# motor_controller_link.net
KiCad netlist of a schematic drawn in EAGLE
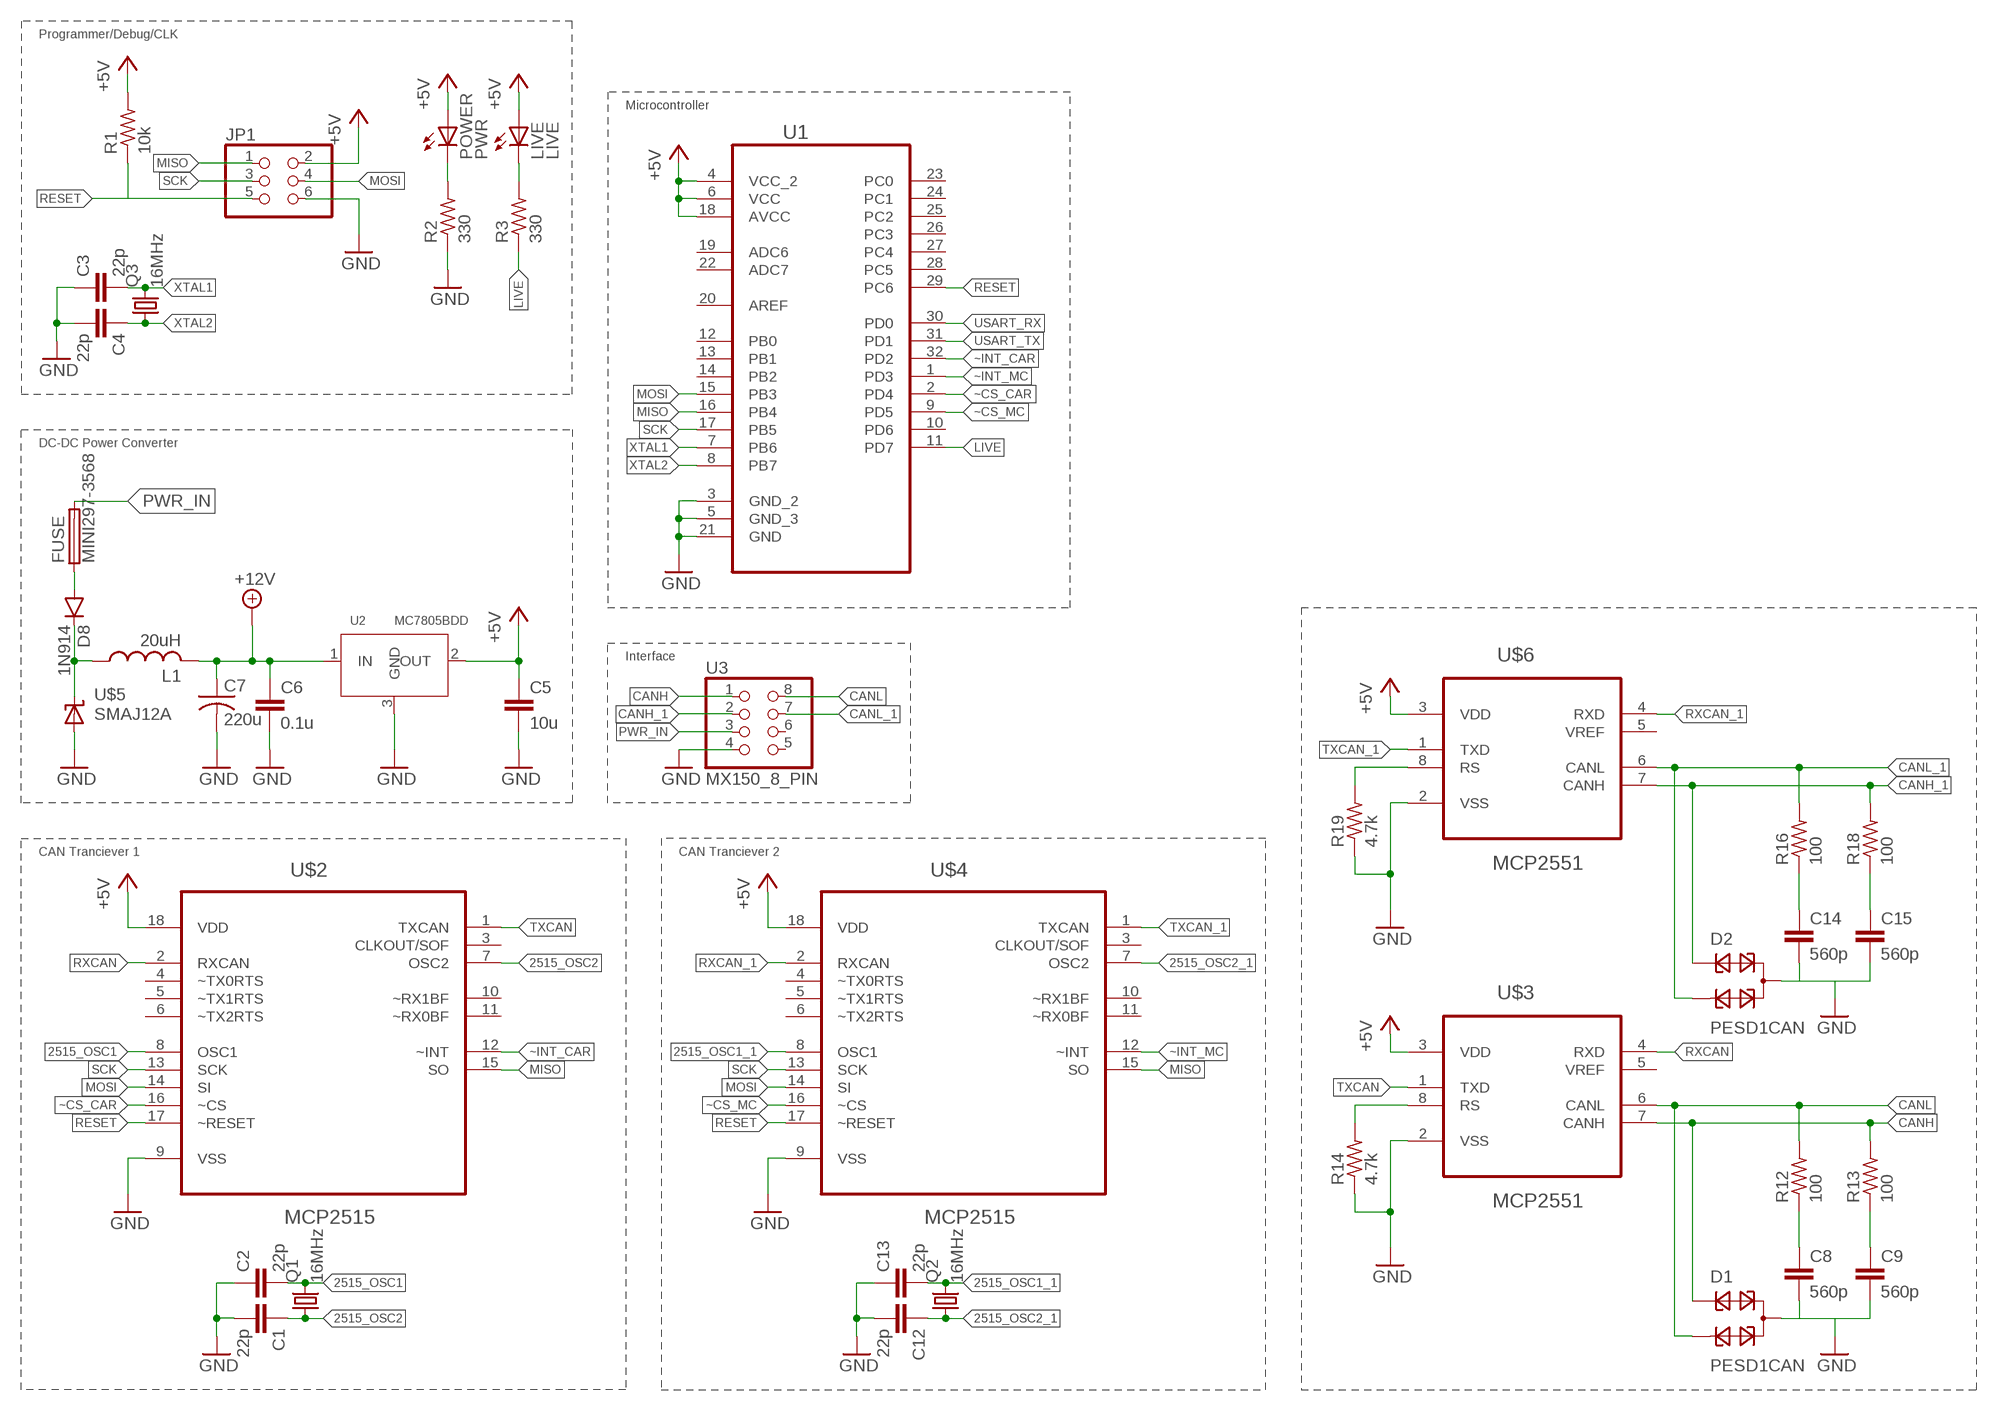
[diagram p0: schematic, sheet 1]

(export (version "E")
  (design (tool "Eeschema 10.0.6"))
  (components
    (comp (ref "C1")
      (value "22p")
      (footprint "eagle-import:C0805K")
      (libsource (lib "eagle-import") (part "resistor_C-EUC0805K"))
    )
    (comp (ref "C2")
      (value "22p")
      (footprint "eagle-import:C0805K")
      (libsource (lib "eagle-import") (part "resistor_C-EUC0805K"))
    )
    (comp (ref "C3")
      (value "22p")
      (footprint "eagle-import:C0805K")
      (libsource (lib "eagle-import") (part "resistor_C-EUC0805K"))
    )
    (comp (ref "C4")
      (value "22p")
      (footprint "eagle-import:C0805K")
      (libsource (lib "eagle-import") (part "resistor_C-EUC0805K"))
    )
    (comp (ref "C5")
      (value "10u")
      (footprint "eagle-import:C0805K")
      (libsource (lib "eagle-import") (part "C-EUC0805K"))
    )
    (comp (ref "C6")
      (value "0.1u")
      (footprint "eagle-import:C0805K")
      (libsource (lib "eagle-import") (part "C-EUC0805K"))
    )
    (comp (ref "C7")
      (value "220u")
      (footprint "eagle-import:C1206")
      (libsource (lib "eagle-import") (part "C1206"))
    )
    (comp (ref "C8")
      (value "560p")
      (footprint "eagle-import:C0805K")
      (libsource (lib "eagle-import") (part "C-EUC0805K"))
    )
    (comp (ref "C9")
      (value "560p")
      (footprint "eagle-import:C0805K")
      (libsource (lib "eagle-import") (part "C-EUC0805K"))
    )
    (comp (ref "C12")
      (value "22p")
      (footprint "eagle-import:C0805K")
      (libsource (lib "eagle-import") (part "resistor_C-EUC0805K"))
    )
    (comp (ref "C13")
      (value "22p")
      (footprint "eagle-import:C0805K")
      (libsource (lib "eagle-import") (part "resistor_C-EUC0805K"))
    )
    (comp (ref "C14")
      (value "560p")
      (footprint "eagle-import:C0805K")
      (libsource (lib "eagle-import") (part "C-EUC0805K"))
    )
    (comp (ref "C15")
      (value "560p")
      (footprint "eagle-import:C0805K")
      (libsource (lib "eagle-import") (part "C-EUC0805K"))
    )
    (comp (ref "D1")
      (value "PESD1CAN")
      (footprint "eagle-import:SOT23")
      (libsource (lib "eagle-import") (part "PESD1CAN"))
    )
    (comp (ref "D2")
      (value "PESD1CAN")
      (footprint "eagle-import:SOT23")
      (libsource (lib "eagle-import") (part "PESD1CAN"))
    )
    (comp (ref "D8")
      (value "1N914")
      (footprint "eagle-import:SMA-DIODE")
      (libsource (lib "eagle-import") (part "DIODESMA"))
    )
    (comp (ref "FUSE")
      (value "MINI297-3568")
      (footprint "eagle-import:3568")
      (libsource (lib "eagle-import") (part "MINI297-3568"))
    )
    (comp (ref "JP1")
      (value "PINHD-2X3")
      (footprint "eagle-import:2X03")
      (libsource (lib "eagle-import") (part "PINHD-2X3"))
    )
    (comp (ref "L1")
      (value "20uH")
      (footprint "eagle-import:MSS7348")
      (libsource (lib "eagle-import") (part "MSS7348"))
    )
    (comp (ref "LIVE")
      (value "LIVE")
      (footprint "eagle-import:SML0805")
      (libsource (lib "eagle-import") (part "LEDSML0805"))
    )
    (comp (ref "POWER")
      (value "PWR")
      (footprint "eagle-import:SML0805")
      (libsource (lib "eagle-import") (part "LEDSML0805"))
    )
    (comp (ref "Q1")
      (value "16MHz")
      (footprint "eagle-import:CTS406")
      (libsource (lib "eagle-import") (part "CRYSTALCTS406"))
    )
    (comp (ref "Q2")
      (value "16MHz")
      (footprint "eagle-import:CTS406")
      (libsource (lib "eagle-import") (part "CRYSTALCTS406"))
    )
    (comp (ref "Q3")
      (value "16MHz")
      (footprint "eagle-import:CTS406")
      (libsource (lib "eagle-import") (part "CRYSTALCTS406"))
    )
    (comp (ref "R1")
      (value "10k")
      (footprint "eagle-import:R0805")
      (libsource (lib "eagle-import") (part "R-US_R0805"))
    )
    (comp (ref "R2")
      (value "330")
      (footprint "eagle-import:R0805")
      (libsource (lib "eagle-import") (part "R-US_R0805"))
    )
    (comp (ref "R3")
      (value "330")
      (footprint "eagle-import:R0805")
      (libsource (lib "eagle-import") (part "R-US_R0805"))
    )
    (comp (ref "R12")
      (value "100")
      (footprint "eagle-import:R0805")
      (libsource (lib "eagle-import") (part "R-US_R0805"))
    )
    (comp (ref "R13")
      (value "100")
      (footprint "eagle-import:R0805")
      (libsource (lib "eagle-import") (part "R-US_R0805"))
    )
    (comp (ref "R14")
      (value "4.7k")
      (footprint "eagle-import:R0805")
      (libsource (lib "eagle-import") (part "R-US_R0805"))
    )
    (comp (ref "R16")
      (value "100")
      (footprint "eagle-import:R0805")
      (libsource (lib "eagle-import") (part "R-US_R0805"))
    )
    (comp (ref "R18")
      (value "100")
      (footprint "eagle-import:R0805")
      (libsource (lib "eagle-import") (part "R-US_R0805"))
    )
    (comp (ref "R19")
      (value "4.7k")
      (footprint "eagle-import:R0805")
      (libsource (lib "eagle-import") (part "R-US_R0805"))
    )
    (comp (ref "U$2")
      (value "MCP2515")
      (footprint "eagle-import:SOIC127P1034X264-18N")
      (fields (field (name "MPN") "MCP2515-I/SO"))
      (libsource (lib "eagle-import") (part "MCP2515-I/SO"))
    )
    (comp (ref "U$3")
      (value "MCP2551")
      (footprint "eagle-import:SOIC127P600X175-8N")
      (fields (field (name "MPN") "MCP2551-I/SN"))
      (libsource (lib "eagle-import") (part "MCP2551-I/SN"))
    )
    (comp (ref "U$4")
      (value "MCP2515")
      (footprint "eagle-import:SOIC127P1034X264-18N")
      (fields (field (name "MPN") "MCP2515-I/SO"))
      (libsource (lib "eagle-import") (part "MCP2515-I/SO"))
    )
    (comp (ref "U$5")
      (value "SMAJ12A")
      (footprint "eagle-import:DO-214AC")
      (libsource (lib "eagle-import") (part "SMAJ12A"))
    )
    (comp (ref "U$6")
      (value "MCP2551")
      (footprint "eagle-import:SOIC127P600X175-8N")
      (fields (field (name "MPN") "MCP2551-I/SN"))
      (libsource (lib "eagle-import") (part "MCP2551-I/SN"))
    )
    (comp (ref "U1")
      (value "ATMEGA328P-AU")
      (footprint "eagle-import:QFP80P900X900X120-32N")
      (libsource (lib "eagle-import") (part "ATMEGA328P-AU"))
    )
    (comp (ref "U2")
      (value "MC7805BDD")
      (footprint "eagle-import:DPAK")
      (libsource (lib "eagle-import") (part "MC7805BDD"))
    )
    (comp (ref "U3")
      (value "MX150_8_PIN")
      (footprint "eagle-import:MX150_8")
      (libsource (lib "eagle-import") (part "MX150_8_PIN"))
    )
  )
  (nets
    (net (code "1") (name "+5V") (class "Default")
      (node (ref "C5") (pin "1") (pinfunction "1_1") (pintype "passive"))
      (node (ref "JP1") (pin "2") (pinfunction "2_2") (pintype "passive"))
      (node (ref "LIVE") (pin "A") (pinfunction "A_A") (pintype "passive"))
      (node (ref "POWER") (pin "A") (pinfunction "A_A") (pintype "passive"))
      (node (ref "R1") (pin "2") (pinfunction "2_2") (pintype "passive"))
      (node (ref "U$2") (pin "18") (pinfunction "VDD_18") (pintype "power_in"))
      (node (ref "U$3") (pin "3") (pinfunction "VDD_3") (pintype "power_in"))
      (node (ref "U$4") (pin "18") (pinfunction "VDD_18") (pintype "power_in"))
      (node (ref "U$6") (pin "3") (pinfunction "VDD_3") (pintype "power_in"))
      (node (ref "U1") (pin "18") (pinfunction "AVCC_18") (pintype "power_in"))
      (node (ref "U1") (pin "4") (pinfunction "VCC_2_4") (pintype "power_in"))
      (node (ref "U1") (pin "6") (pinfunction "VCC_6") (pintype "power_in"))
      (node (ref "U2") (pin "2") (pinfunction "OUT_2") (pintype "bidirectional"))
    )
    (net (code "2") (name "+12V") (class "Default")
      (node (ref "C6") (pin "1") (pinfunction "1_1") (pintype "passive"))
      (node (ref "C7") (pin "1") (pinfunction "1_1") (pintype "passive"))
      (node (ref "L1") (pin "P$2") (pinfunction "2_P$2") (pintype "passive"))
      (node (ref "U2") (pin "1") (pinfunction "IN_1") (pintype "bidirectional"))
    )
    (net (code "3") (name "/~{CS_CAR}") (class "Default")
      (node (ref "U$2") (pin "16") (pinfunction "~{CS}_16") (pintype "input"))
      (node (ref "U1") (pin "2") (pinfunction "PD4_2") (pintype "bidirectional"))
    )
    (net (code "4") (name "/~{CS_MC}") (class "Default")
      (node (ref "U$4") (pin "16") (pinfunction "~{CS}_16") (pintype "input"))
      (node (ref "U1") (pin "9") (pinfunction "PD5_9") (pintype "bidirectional"))
    )
    (net (code "5") (name "/~{INT_CAR}") (class "Default")
      (node (ref "U$2") (pin "12") (pinfunction "~{INT}_12") (pintype "output"))
      (node (ref "U1") (pin "32") (pinfunction "PD2_32") (pintype "bidirectional"))
    )
    (net (code "6") (name "/~{INT_MC}") (class "Default")
      (node (ref "U$4") (pin "12") (pinfunction "~{INT}_12") (pintype "output"))
      (node (ref "U1") (pin "1") (pinfunction "PD3_1") (pintype "bidirectional"))
    )
    (net (code "7") (name "2515_OSC1") (class "Default")
      (node (ref "C2") (pin "2") (pinfunction "2_2") (pintype "passive"))
      (node (ref "Q1") (pin "3") (pinfunction "2_3") (pintype "passive"))
      (node (ref "U$2") (pin "8") (pinfunction "OSC1_8") (pintype "input"))
    )
    (net (code "8") (name "2515_OSC1_1") (class "Default")
      (node (ref "C13") (pin "2") (pinfunction "2_2") (pintype "passive"))
      (node (ref "Q2") (pin "3") (pinfunction "2_3") (pintype "passive"))
      (node (ref "U$4") (pin "8") (pinfunction "OSC1_8") (pintype "input"))
    )
    (net (code "9") (name "2515_OSC2") (class "Default")
      (node (ref "C1") (pin "1") (pinfunction "1_1") (pintype "passive"))
      (node (ref "Q1") (pin "1") (pinfunction "1_1") (pintype "passive"))
      (node (ref "U$2") (pin "7") (pinfunction "OSC2_7") (pintype "output"))
    )
    (net (code "10") (name "2515_OSC2_1") (class "Default")
      (node (ref "C12") (pin "1") (pinfunction "1_1") (pintype "passive"))
      (node (ref "Q2") (pin "1") (pinfunction "1_1") (pintype "passive"))
      (node (ref "U$4") (pin "7") (pinfunction "OSC2_7") (pintype "output"))
    )
    (net (code "11") (name "CANH") (class "Default")
      (node (ref "D1") (pin "1") (pinfunction "1_1") (pintype "passive"))
      (node (ref "R13") (pin "2") (pinfunction "2_2") (pintype "passive"))
      (node (ref "U$3") (pin "7") (pinfunction "CANH_7") (pintype "bidirectional"))
      (node (ref "U3") (pin "1") (pinfunction "1_1") (pintype "passive"))
    )
    (net (code "12") (name "CANH_1") (class "Default")
      (node (ref "D2") (pin "1") (pinfunction "1_1") (pintype "passive"))
      (node (ref "R18") (pin "2") (pinfunction "2_2") (pintype "passive"))
      (node (ref "U$6") (pin "7") (pinfunction "CANH_7") (pintype "bidirectional"))
      (node (ref "U3") (pin "2") (pinfunction "3_2") (pintype "passive"))
    )
    (net (code "13") (name "CANL") (class "Default")
      (node (ref "D1") (pin "2") (pinfunction "2_2") (pintype "passive"))
      (node (ref "R12") (pin "2") (pinfunction "2_2") (pintype "passive"))
      (node (ref "U$3") (pin "6") (pinfunction "CANL_6") (pintype "bidirectional"))
      (node (ref "U3") (pin "8") (pinfunction "2_8") (pintype "passive"))
    )
    (net (code "14") (name "CANL_1") (class "Default")
      (node (ref "D2") (pin "2") (pinfunction "2_2") (pintype "passive"))
      (node (ref "R16") (pin "2") (pinfunction "2_2") (pintype "passive"))
      (node (ref "U$6") (pin "6") (pinfunction "CANL_6") (pintype "bidirectional"))
      (node (ref "U3") (pin "7") (pinfunction "4_7") (pintype "passive"))
    )
    (net (code "15") (name "GND") (class "Default")
      (node (ref "C1") (pin "2") (pinfunction "2_2") (pintype "passive"))
      (node (ref "C12") (pin "2") (pinfunction "2_2") (pintype "passive"))
      (node (ref "C13") (pin "1") (pinfunction "1_1") (pintype "passive"))
      (node (ref "C14") (pin "2") (pinfunction "2_2") (pintype "passive"))
      (node (ref "C15") (pin "2") (pinfunction "2_2") (pintype "passive"))
      (node (ref "C2") (pin "1") (pinfunction "1_1") (pintype "passive"))
      (node (ref "C3") (pin "1") (pinfunction "1_1") (pintype "passive"))
      (node (ref "C4") (pin "2") (pinfunction "2_2") (pintype "passive"))
      (node (ref "C5") (pin "2") (pinfunction "2_2") (pintype "passive"))
      (node (ref "C6") (pin "2") (pinfunction "2_2") (pintype "passive"))
      (node (ref "C7") (pin "2") (pinfunction "2_2") (pintype "passive"))
      (node (ref "C8") (pin "2") (pinfunction "2_2") (pintype "passive"))
      (node (ref "C9") (pin "2") (pinfunction "2_2") (pintype "passive"))
      (node (ref "D1") (pin "3") (pinfunction "3_3") (pintype "passive"))
      (node (ref "D2") (pin "3") (pinfunction "3_3") (pintype "passive"))
      (node (ref "JP1") (pin "6") (pinfunction "6_6") (pintype "passive"))
      (node (ref "R14") (pin "1") (pinfunction "1_1") (pintype "passive"))
      (node (ref "R19") (pin "1") (pinfunction "1_1") (pintype "passive"))
      (node (ref "R2") (pin "1") (pinfunction "1_1") (pintype "passive"))
      (node (ref "U$2") (pin "9") (pinfunction "VSS_9") (pintype "power_in"))
      (node (ref "U$3") (pin "2") (pinfunction "VSS_2") (pintype "passive"))
      (node (ref "U$4") (pin "9") (pinfunction "VSS_9") (pintype "power_in"))
      (node (ref "U$5") (pin "A") (pinfunction "A_A") (pintype "passive"))
      (node (ref "U$6") (pin "2") (pinfunction "VSS_2") (pintype "passive"))
      (node (ref "U1") (pin "21") (pinfunction "GND_21") (pintype "passive"))
      (node (ref "U1") (pin "3") (pinfunction "GND_2_3") (pintype "passive"))
      (node (ref "U1") (pin "5") (pinfunction "GND_3_5") (pintype "passive"))
      (node (ref "U2") (pin "3") (pinfunction "GND_3") (pintype "bidirectional"))
      (node (ref "U3") (pin "4") (pinfunction "7_4") (pintype "passive"))
    )
    (net (code "16") (name "LIVE") (class "Default")
      (node (ref "R3") (pin "1") (pinfunction "1_1") (pintype "passive"))
      (node (ref "U1") (pin "11") (pinfunction "PD7_11") (pintype "bidirectional"))
    )
    (net (code "17") (name "MISO") (class "Default")
      (node (ref "JP1") (pin "1") (pinfunction "1_1") (pintype "passive"))
      (node (ref "U$2") (pin "15") (pinfunction "SO_15") (pintype "output"))
      (node (ref "U$4") (pin "15") (pinfunction "SO_15") (pintype "output"))
      (node (ref "U1") (pin "16") (pinfunction "PB4_16") (pintype "bidirectional"))
    )
    (net (code "18") (name "MOSI") (class "Default")
      (node (ref "JP1") (pin "4") (pinfunction "4_4") (pintype "passive"))
      (node (ref "U$2") (pin "14") (pinfunction "SI_14") (pintype "input"))
      (node (ref "U$4") (pin "14") (pinfunction "SI_14") (pintype "input"))
      (node (ref "U1") (pin "15") (pinfunction "PB3_15") (pintype "bidirectional"))
    )
    (net (code "19") (name "Net-(C8-Pad1)") (class "Default")
      (node (ref "C8") (pin "1") (pinfunction "1_1") (pintype "passive"))
      (node (ref "R12") (pin "1") (pinfunction "1_1") (pintype "passive"))
    )
    (net (code "20") (name "Net-(C9-Pad1)") (class "Default")
      (node (ref "C9") (pin "1") (pinfunction "1_1") (pintype "passive"))
      (node (ref "R13") (pin "1") (pinfunction "1_1") (pintype "passive"))
    )
    (net (code "21") (name "Net-(C14-Pad1)") (class "Default")
      (node (ref "C14") (pin "1") (pinfunction "1_1") (pintype "passive"))
      (node (ref "R16") (pin "1") (pinfunction "1_1") (pintype "passive"))
    )
    (net (code "22") (name "Net-(C15-Pad1)") (class "Default")
      (node (ref "C15") (pin "1") (pinfunction "1_1") (pintype "passive"))
      (node (ref "R18") (pin "1") (pinfunction "1_1") (pintype "passive"))
    )
    (net (code "23") (name "Net-(D8-PadA)") (class "Default")
      (node (ref "D8") (pin "A") (pinfunction "A_A") (pintype "passive"))
      (node (ref "FUSE") (pin "P$1") (pinfunction "1_P$1") (pintype "passive"))
      (node (ref "FUSE") (pin "P$4") (pinfunction "1_P$4") (pintype "passive"))
    )
    (net (code "24") (name "Net-(L1-1)") (class "Default")
      (node (ref "D8") (pin "C") (pinfunction "C_C") (pintype "passive"))
      (node (ref "L1") (pin "P$1") (pinfunction "1_P$1") (pintype "passive"))
      (node (ref "U$5") (pin "C") (pinfunction "C_C") (pintype "passive"))
    )
    (net (code "25") (name "Net-(LIVE-PadC)") (class "Default")
      (node (ref "LIVE") (pin "C") (pinfunction "C_C") (pintype "passive"))
      (node (ref "R3") (pin "2") (pinfunction "2_2") (pintype "passive"))
    )
    (net (code "26") (name "Net-(POWER-PadC)") (class "Default")
      (node (ref "POWER") (pin "C") (pinfunction "C_C") (pintype "passive"))
      (node (ref "R2") (pin "2") (pinfunction "2_2") (pintype "passive"))
    )
    (net (code "27") (name "Net-(U$3-RS)") (class "Default")
      (node (ref "R14") (pin "2") (pinfunction "2_2") (pintype "passive"))
      (node (ref "U$3") (pin "8") (pinfunction "RS_8") (pintype "input"))
    )
    (net (code "28") (name "Net-(U$6-RS)") (class "Default")
      (node (ref "R19") (pin "2") (pinfunction "2_2") (pintype "passive"))
      (node (ref "U$6") (pin "8") (pinfunction "RS_8") (pintype "input"))
    )
    (net (code "29") (name "PWR_IN") (class "Default")
      (node (ref "FUSE") (pin "P$2") (pinfunction "2_P$2") (pintype "passive"))
      (node (ref "FUSE") (pin "P$3") (pinfunction "2_P$3") (pintype "passive"))
      (node (ref "U3") (pin "3") (pinfunction "5_3") (pintype "passive"))
    )
    (net (code "30") (name "RESET") (class "Default")
      (node (ref "JP1") (pin "5") (pinfunction "5_5") (pintype "passive"))
      (node (ref "R1") (pin "1") (pinfunction "1_1") (pintype "passive"))
      (node (ref "U$2") (pin "17") (pinfunction "~{RESET}_17") (pintype "input"))
      (node (ref "U$4") (pin "17") (pinfunction "~{RESET}_17") (pintype "input"))
      (node (ref "U1") (pin "29") (pinfunction "PC6_29") (pintype "bidirectional"))
    )
    (net (code "31") (name "RXCAN") (class "Default")
      (node (ref "U$2") (pin "2") (pinfunction "RXCAN_2") (pintype "input"))
      (node (ref "U$3") (pin "4") (pinfunction "RXD_4") (pintype "output"))
    )
    (net (code "32") (name "RXCAN_1") (class "Default")
      (node (ref "U$4") (pin "2") (pinfunction "RXCAN_2") (pintype "input"))
      (node (ref "U$6") (pin "4") (pinfunction "RXD_4") (pintype "output"))
    )
    (net (code "33") (name "SCK") (class "Default")
      (node (ref "JP1") (pin "3") (pinfunction "3_3") (pintype "passive"))
      (node (ref "U$2") (pin "13") (pinfunction "SCK_13") (pintype "input"))
      (node (ref "U$4") (pin "13") (pinfunction "SCK_13") (pintype "input"))
      (node (ref "U1") (pin "17") (pinfunction "PB5_17") (pintype "bidirectional"))
    )
    (net (code "34") (name "TXCAN") (class "Default")
      (node (ref "U$2") (pin "1") (pinfunction "TXCAN_1") (pintype "output"))
      (node (ref "U$3") (pin "1") (pinfunction "TXD_1") (pintype "input"))
    )
    (net (code "35") (name "TXCAN_1") (class "Default")
      (node (ref "U$4") (pin "1") (pinfunction "TXCAN_1") (pintype "output"))
      (node (ref "U$6") (pin "1") (pinfunction "TXD_1") (pintype "input"))
    )
    (net (code "36") (name "USART_RX") (class "Default")
      (node (ref "U1") (pin "30") (pinfunction "PD0_30") (pintype "bidirectional"))
    )
    (net (code "37") (name "USART_TX") (class "Default")
      (node (ref "U1") (pin "31") (pinfunction "PD1_31") (pintype "bidirectional"))
    )
    (net (code "38") (name "XTAL1") (class "Default")
      (node (ref "C3") (pin "2") (pinfunction "2_2") (pintype "passive"))
      (node (ref "Q3") (pin "3") (pinfunction "2_3") (pintype "passive"))
      (node (ref "U1") (pin "7") (pinfunction "PB6_7") (pintype "bidirectional"))
    )
    (net (code "39") (name "XTAL2") (class "Default")
      (node (ref "C4") (pin "1") (pinfunction "1_1") (pintype "passive"))
      (node (ref "Q3") (pin "1") (pinfunction "1_1") (pintype "passive"))
      (node (ref "U1") (pin "8") (pinfunction "PB7_8") (pintype "bidirectional"))
    )
    (net (code "40") (name "unconnected-(U$2-CLKOUT{slash}SOF-Pad3)") (class "Default")
      (node (ref "U$2") (pin "3") (pinfunction "CLKOUT/SOF_3") (pintype "output"))
    )
    (net (code "41") (name "unconnected-(U$2-~{RX0BF}-Pad11)") (class "Default")
      (node (ref "U$2") (pin "11") (pinfunction "~{RX0BF}_11") (pintype "output"))
    )
    (net (code "42") (name "unconnected-(U$2-~{RX1BF}-Pad10)") (class "Default")
      (node (ref "U$2") (pin "10") (pinfunction "~{RX1BF}_10") (pintype "output"))
    )
    (net (code "43") (name "unconnected-(U$2-~{TX0RTS}-Pad4)") (class "Default")
      (node (ref "U$2") (pin "4") (pinfunction "~{TX0RTS}_4") (pintype "input"))
    )
    (net (code "44") (name "unconnected-(U$2-~{TX1RTS}-Pad5)") (class "Default")
      (node (ref "U$2") (pin "5") (pinfunction "~{TX1RTS}_5") (pintype "input"))
    )
    (net (code "45") (name "unconnected-(U$2-~{TX2RTS}-Pad6)") (class "Default")
      (node (ref "U$2") (pin "6") (pinfunction "~{TX2RTS}_6") (pintype "input"))
    )
    (net (code "46") (name "unconnected-(U$3-VREF-Pad5)") (class "Default")
      (node (ref "U$3") (pin "5") (pinfunction "VREF_5") (pintype "output"))
    )
    (net (code "47") (name "unconnected-(U$4-CLKOUT{slash}SOF-Pad3)") (class "Default")
      (node (ref "U$4") (pin "3") (pinfunction "CLKOUT/SOF_3") (pintype "output"))
    )
    (net (code "48") (name "unconnected-(U$4-~{RX0BF}-Pad11)") (class "Default")
      (node (ref "U$4") (pin "11") (pinfunction "~{RX0BF}_11") (pintype "output"))
    )
    (net (code "49") (name "unconnected-(U$4-~{RX1BF}-Pad10)") (class "Default")
      (node (ref "U$4") (pin "10") (pinfunction "~{RX1BF}_10") (pintype "output"))
    )
    (net (code "50") (name "unconnected-(U$4-~{TX0RTS}-Pad4)") (class "Default")
      (node (ref "U$4") (pin "4") (pinfunction "~{TX0RTS}_4") (pintype "input"))
    )
    (net (code "51") (name "unconnected-(U$4-~{TX1RTS}-Pad5)") (class "Default")
      (node (ref "U$4") (pin "5") (pinfunction "~{TX1RTS}_5") (pintype "input"))
    )
    (net (code "52") (name "unconnected-(U$4-~{TX2RTS}-Pad6)") (class "Default")
      (node (ref "U$4") (pin "6") (pinfunction "~{TX2RTS}_6") (pintype "input"))
    )
    (net (code "53") (name "unconnected-(U$6-VREF-Pad5)") (class "Default")
      (node (ref "U$6") (pin "5") (pinfunction "VREF_5") (pintype "output"))
    )
    (net (code "54") (name "unconnected-(U1-ADC6-Pad19)") (class "Default")
      (node (ref "U1") (pin "19") (pinfunction "ADC6_19") (pintype "input"))
    )
    (net (code "55") (name "unconnected-(U1-ADC7-Pad22)") (class "Default")
      (node (ref "U1") (pin "22") (pinfunction "ADC7_22") (pintype "input"))
    )
    (net (code "56") (name "unconnected-(U1-AREF-Pad20)") (class "Default")
      (node (ref "U1") (pin "20") (pinfunction "AREF_20") (pintype "input"))
    )
    (net (code "57") (name "unconnected-(U1-PB0-Pad12)") (class "Default")
      (node (ref "U1") (pin "12") (pinfunction "PB0_12") (pintype "bidirectional"))
    )
    (net (code "58") (name "unconnected-(U1-PB1-Pad13)") (class "Default")
      (node (ref "U1") (pin "13") (pinfunction "PB1_13") (pintype "bidirectional"))
    )
    (net (code "59") (name "unconnected-(U1-PB2-Pad14)") (class "Default")
      (node (ref "U1") (pin "14") (pinfunction "PB2_14") (pintype "bidirectional"))
    )
    (net (code "60") (name "unconnected-(U1-PC0-Pad23)") (class "Default")
      (node (ref "U1") (pin "23") (pinfunction "PC0_23") (pintype "bidirectional"))
    )
    (net (code "61") (name "unconnected-(U1-PC1-Pad24)") (class "Default")
      (node (ref "U1") (pin "24") (pinfunction "PC1_24") (pintype "bidirectional"))
    )
    (net (code "62") (name "unconnected-(U1-PC2-Pad25)") (class "Default")
      (node (ref "U1") (pin "25") (pinfunction "PC2_25") (pintype "bidirectional"))
    )
    (net (code "63") (name "unconnected-(U1-PC3-Pad26)") (class "Default")
      (node (ref "U1") (pin "26") (pinfunction "PC3_26") (pintype "bidirectional"))
    )
    (net (code "64") (name "unconnected-(U1-PC4-Pad27)") (class "Default")
      (node (ref "U1") (pin "27") (pinfunction "PC4_27") (pintype "bidirectional"))
    )
    (net (code "65") (name "unconnected-(U1-PC5-Pad28)") (class "Default")
      (node (ref "U1") (pin "28") (pinfunction "PC5_28") (pintype "bidirectional"))
    )
    (net (code "66") (name "unconnected-(U1-PD6-Pad10)") (class "Default")
      (node (ref "U1") (pin "10") (pinfunction "PD6_10") (pintype "bidirectional"))
    )
    (net (code "67") (name "unconnected-(U3-8-Pad5)") (class "Default")
      (node (ref "U3") (pin "5") (pinfunction "8_5") (pintype "passive"))
    )
    (net (code "68") (name "unconnected-(U3-Pad6)") (class "Default")
      (node (ref "U3") (pin "6") (pinfunction "6_6") (pintype "passive"))
    )
  )
)
